# USB_mega8.net
KiCad netlist of a schematic drawn in Altium Designer
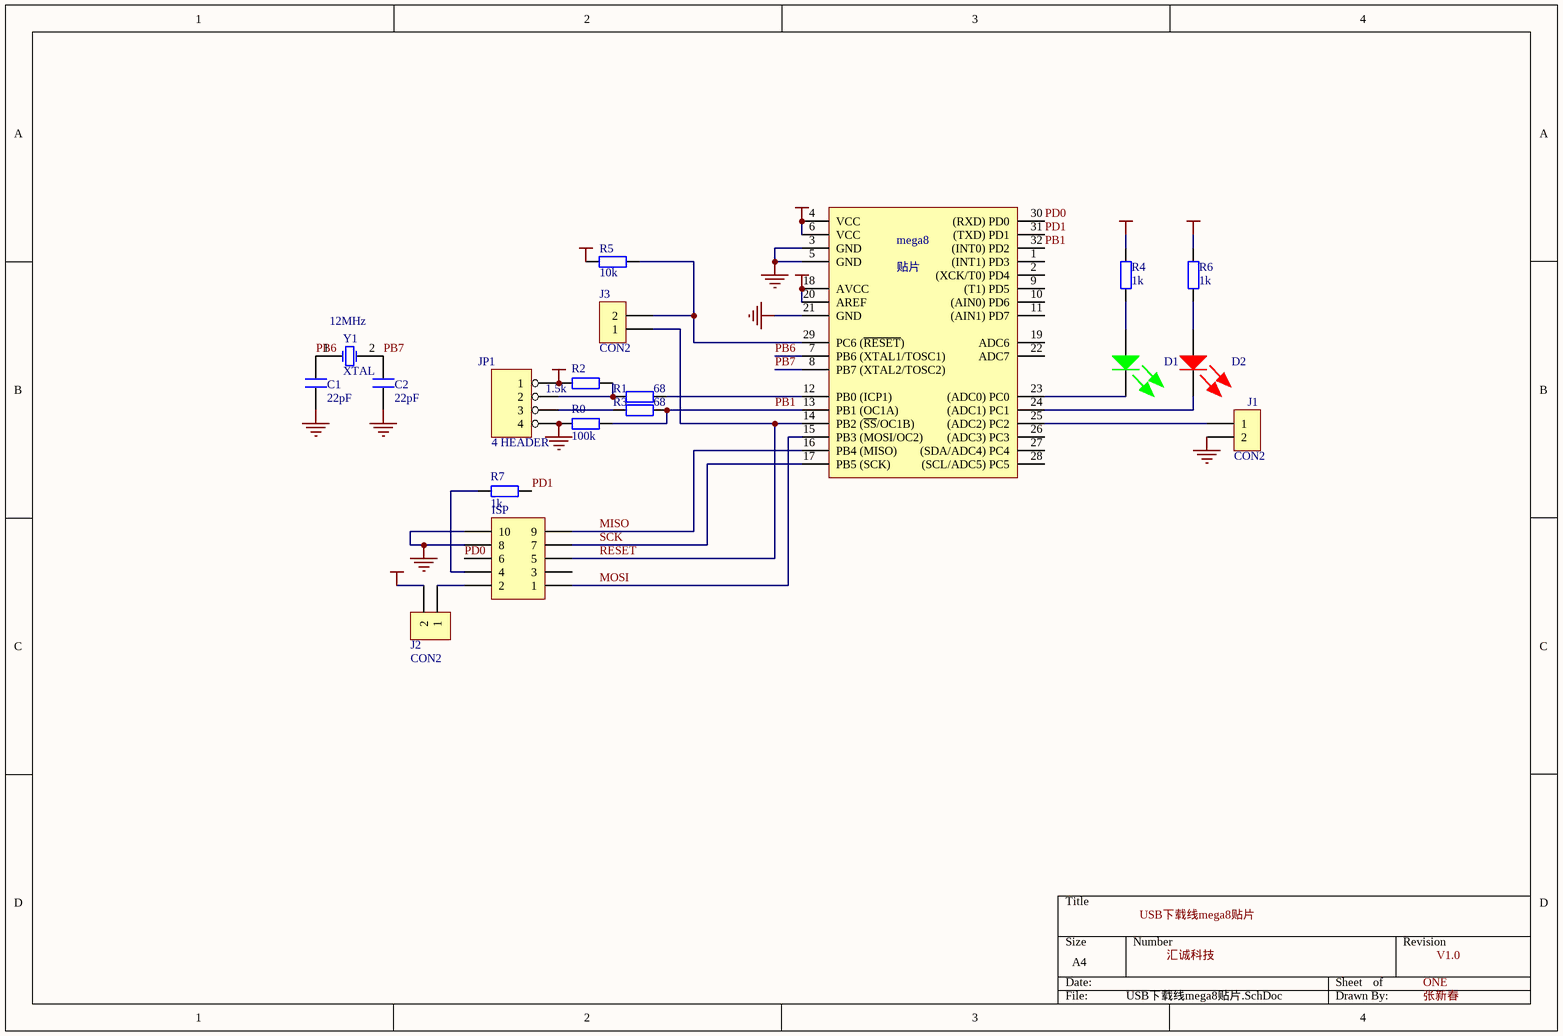
[diagram p0: USB下载线mega8贴片.SchDoc]

(export (version "E")
  (design (tool "Eeschema 10.0.6"))
  (components
    (comp (ref "C1")
      (value "22pF")
      (footprint "HDR1X2")
      (description "Capacitor SMD1206")
      (libsource (lib "*") (part "CAPSMD"))
    )
    (comp (ref "C2")
      (value "22pF")
      (footprint "HDR1X2")
      (description "Capacitor SMD1206")
      (libsource (lib "*") (part "CAPSMD"))
    )
    (comp (ref "D1")
      (value "~")
      (footprint "HDR1X2")
      (description "Zöld Led 3mm")
      (libsource (lib "*") (part "LED Zöld"))
    )
    (comp (ref "D2")
      (value "~")
      (footprint "HDR1X2")
      (description "Piros Led 3mm")
      (libsource (lib "*") (part "LED Piros"))
    )
    (comp (ref "ISP")
      (value "~")
      (footprint "HDR2X5")
      (description "Header, 5-Pin, Dual row, Right Angle")
      (fields (field (name "MANUFACTURER") "Generic Components"))
      (libsource (lib "*") (part "MLW10A"))
    )
    (comp (ref "J1")
      (value "CON2")
      (footprint "HDR1X2")
      (description "Connector")
      (libsource (lib "") (part "CON2_2"))
    )
    (comp (ref "J2")
      (value "CON2")
      (footprint "HDR1X2")
      (description "Connector")
      (libsource (lib "") (part "CON2_1"))
    )
    (comp (ref "J3")
      (value "CON2")
      (footprint "HDR1X2")
      (description "Connector")
      (libsource (lib "*") (part "CON2"))
    )
    (comp (ref "JP1")
      (value "4 HEADER")
      (footprint "USB")
      (description "4 Pin Header")
      (libsource (lib "*") (part "4 HEADER"))
    )
    (comp (ref "mega8")
      (value "贴片")
      (footprint "TQFP-32_0.8/7×7mm")
      (description "8 位微处理器/32引脚")
      (fields (field (name "发布者") "磊元工作室"))
      (libsource (lib "微控制处理器") (part "ATmega8-A"))
    )
    (comp (ref "R0")
      (value "100k")
      (footprint "HDR1X2")
      (description "Resistor SMD1206, 1% fémréteg")
      (libsource (lib "*") (part "RES"))
    )
    (comp (ref "R1")
      (value "68")
      (footprint "HDR1X2")
      (description "Resistor SMD1206, 1% fémréteg")
      (libsource (lib "*") (part "RES"))
    )
    (comp (ref "R2")
      (value "1.5k")
      (footprint "HDR1X2")
      (description "Resistor SMD1206, 1% fémréteg")
      (libsource (lib "*") (part "RES"))
    )
    (comp (ref "R3")
      (value "68")
      (footprint "HDR1X2")
      (description "Resistor SMD1206, 1% fémréteg")
      (libsource (lib "*") (part "RES"))
    )
    (comp (ref "R4")
      (value "1k")
      (footprint "HDR1X2")
      (description "Resistor SMD1206, 1% fémréteg")
      (libsource (lib "*") (part "RES"))
    )
    (comp (ref "R5")
      (value "10k")
      (footprint "HDR1X2")
      (description "Resistor SMD1206, 1% fémréteg")
      (libsource (lib "*") (part "RES"))
    )
    (comp (ref "R6")
      (value "1k")
      (footprint "HDR1X2")
      (description "Resistor SMD1206, 1% fémréteg")
      (libsource (lib "*") (part "RES"))
    )
    (comp (ref "R7")
      (value "1k")
      (footprint "HDR1X2")
      (description "Resistor SMD1206, 1% fémréteg")
      (libsource (lib "*") (part "RES"))
    )
    (comp (ref "Y1")
      (value "XTAL")
      (footprint "SPST-2")
      (description "Crystal Oscillator")
      (fields
        (field (name "MANUFACTURER") "Generic Components")
        (field (name "ALTIUM_VALUE") "12MHz")
        (field (name "PUBLISHER") "Altium Hobart Technology Centre")
      )
      (libsource (lib "*") (part "XTAL"))
    )
  )
  (nets
    (net (code "1") (name "/MISO") (class "Default")
      (node (ref "ISP") (pin "9") (pinfunction "9_9") (pintype "passive"))
      (node (ref "mega8") (pin "16") (pinfunction "PB4_(MISO)_16") (pintype "passive"))
    )
    (net (code "2") (name "/MOSI") (class "Default")
      (node (ref "ISP") (pin "1") (pinfunction "1_1") (pintype "passive"))
      (node (ref "mega8") (pin "15") (pinfunction "PB3_(MOSI/OC2)_15") (pintype "passive"))
    )
    (net (code "4") (name "/PB1") (class "Default")
      (node (ref "R0") (pin "2") (pinfunction "2_2") (pintype "passive"))
      (node (ref "R3") (pin "1") (pinfunction "1_1") (pintype "passive"))
      (node (ref "mega8") (pin "13") (pinfunction "PB1_(OC1A)_13") (pintype "passive"))
      (node (ref "mega8") (pin "32") (pinfunction "(INT0)_PD2_32") (pintype "passive"))
    )
    (net (code "5") (name "/PB6") (class "Default")
      (node (ref "C1") (pin "2") (pinfunction "2_2") (pintype "passive"))
      (node (ref "Y1") (pin "1") (pinfunction "OSC1_1") (pintype "passive"))
      (node (ref "mega8") (pin "7") (pinfunction "PB6_(XTAL1/TOSC1)_7") (pintype "passive"))
    )
    (net (code "6") (name "/PB7") (class "Default")
      (node (ref "C2") (pin "2") (pinfunction "2_2") (pintype "passive"))
      (node (ref "Y1") (pin "2") (pinfunction "OSC2_2") (pintype "passive"))
      (node (ref "mega8") (pin "8") (pinfunction "PB7_(XTAL2/TOSC2)_8") (pintype "passive"))
    )
    (net (code "7") (name "/PD0") (class "Default")
      (node (ref "ISP") (pin "6") (pinfunction "6_6") (pintype "passive"))
      (node (ref "mega8") (pin "30") (pinfunction "(RXD)_PD0_30") (pintype "passive"))
    )
    (net (code "8") (name "/PD1") (class "Default")
      (node (ref "R7") (pin "2") (pinfunction "2_2") (pintype "passive"))
      (node (ref "mega8") (pin "31") (pinfunction "(TXD)_PD1_31") (pintype "passive"))
    )
    (net (code "9") (name "/RESET") (class "Default")
      (node (ref "ISP") (pin "5") (pinfunction "5_5") (pintype "passive"))
      (node (ref "J3") (pin "1") (pinfunction "1_1") (pintype "passive"))
      (node (ref "mega8") (pin "14") (pinfunction "PB2_(~{SS}/OC1B)_14") (pintype "passive"))
    )
    (net (code "10") (name "/SCK") (class "Default")
      (node (ref "ISP") (pin "7") (pinfunction "7_7") (pintype "passive"))
      (node (ref "mega8") (pin "17") (pinfunction "PB5_(SCK)_17") (pintype "passive"))
    )
    (net (code "15") (name "GND") (class "Default")
      (node (ref "C1") (pin "1") (pinfunction "1_1") (pintype "passive"))
      (node (ref "C2") (pin "1") (pinfunction "1_1") (pintype "passive"))
      (node (ref "ISP") (pin "10") (pinfunction "10_10") (pintype "passive"))
      (node (ref "ISP") (pin "8") (pinfunction "8_8") (pintype "passive"))
      (node (ref "J1") (pin "2") (pinfunction "2_2") (pintype "passive"))
      (node (ref "JP1") (pin "4") (pinfunction "4_4") (pintype "passive"))
      (node (ref "R0") (pin "1") (pinfunction "1_1") (pintype "passive"))
      (node (ref "mega8") (pin "21") (pinfunction "GND_21") (pintype "passive"))
      (node (ref "mega8") (pin "3") (pinfunction "GND_3") (pintype "passive"))
      (node (ref "mega8") (pin "5") (pinfunction "GND_5") (pintype "passive"))
    )
    (net (code "16") (name "Net-(D1-Pad1)") (class "Default")
      (node (ref "D1") (pin "1") (pinfunction "1_1") (pintype "passive"))
      (node (ref "R4") (pin "1") (pinfunction "1_1") (pintype "passive"))
    )
    (net (code "17") (name "Net-(D2-Pad1)") (class "Default")
      (node (ref "D2") (pin "1") (pinfunction "1_1") (pintype "passive"))
      (node (ref "R6") (pin "1") (pinfunction "1_1") (pintype "passive"))
    )
    (net (code "18") (name "Net-(ISP-Pad2)") (class "Default")
      (node (ref "ISP") (pin "2") (pinfunction "2_2") (pintype "passive"))
      (node (ref "J2") (pin "1") (pinfunction "1_1") (pintype "passive"))
    )
    (net (code "19") (name "Net-(ISP-Pad4)") (class "Default")
      (node (ref "ISP") (pin "4") (pinfunction "4_4") (pintype "passive"))
      (node (ref "R7") (pin "1") (pinfunction "1_1") (pintype "passive"))
    )
    (net (code "20") (name "Net-(JP1-Pad2)") (class "Default")
      (node (ref "JP1") (pin "2") (pinfunction "2_2") (pintype "passive"))
      (node (ref "R1") (pin "1") (pinfunction "1_1") (pintype "passive"))
      (node (ref "R2") (pin "1") (pinfunction "1_1") (pintype "passive"))
    )
    (net (code "21") (name "Net-(JP1-Pad3)") (class "Default")
      (node (ref "JP1") (pin "3") (pinfunction "3_3") (pintype "passive"))
      (node (ref "R3") (pin "2") (pinfunction "2_2") (pintype "passive"))
    )
    (net (code "22") (name "Net-(mega8-(ADC0)_PC0)") (class "Default")
      (node (ref "D1") (pin "2") (pinfunction "2_2") (pintype "passive"))
      (node (ref "mega8") (pin "23") (pinfunction "(ADC0)_PC0_23") (pintype "passive"))
    )
    (net (code "23") (name "Net-(mega8-(ADC1)_PC1)") (class "Default")
      (node (ref "D2") (pin "2") (pinfunction "2_2") (pintype "passive"))
      (node (ref "mega8") (pin "24") (pinfunction "(ADC1)_PC1_24") (pintype "passive"))
    )
    (net (code "24") (name "Net-(mega8-(ADC2)_PC2)") (class "Default")
      (node (ref "J1") (pin "1") (pinfunction "1_1") (pintype "passive"))
      (node (ref "mega8") (pin "25") (pinfunction "(ADC2)_PC2_25") (pintype "passive"))
    )
    (net (code "25") (name "Net-(mega8-PB0_(ICP1))") (class "Default")
      (node (ref "R1") (pin "2") (pinfunction "2_2") (pintype "passive"))
      (node (ref "mega8") (pin "12") (pinfunction "PB0_(ICP1)_12") (pintype "passive"))
    )
    (net (code "26") (name "Net-(mega8-PC6_(~{RESET}))") (class "Default")
      (node (ref "J3") (pin "2") (pinfunction "2_2") (pintype "passive"))
      (node (ref "R5") (pin "1") (pinfunction "1_1") (pintype "passive"))
      (node (ref "mega8") (pin "29") (pinfunction "PC6_(~{RESET})_29") (pintype "passive"))
    )
    (net (code "27") (name "VCC") (class "Default")
      (node (ref "J2") (pin "2") (pinfunction "2_2") (pintype "passive"))
      (node (ref "JP1") (pin "1") (pinfunction "1_1") (pintype "passive"))
      (node (ref "R2") (pin "2") (pinfunction "2_2") (pintype "passive"))
      (node (ref "R4") (pin "2") (pinfunction "2_2") (pintype "passive"))
      (node (ref "R5") (pin "2") (pinfunction "2_2") (pintype "passive"))
      (node (ref "R6") (pin "2") (pinfunction "2_2") (pintype "passive"))
      (node (ref "mega8") (pin "18") (pinfunction "AVCC_18") (pintype "passive"))
      (node (ref "mega8") (pin "20") (pinfunction "AREF_20") (pintype "passive"))
      (node (ref "mega8") (pin "4") (pinfunction "VCC_4") (pintype "passive"))
      (node (ref "mega8") (pin "6") (pinfunction "VCC_6") (pintype "passive"))
    )
    (net (code "28") (name "unconnected-(ISP-Pad3)") (class "Default")
      (node (ref "ISP") (pin "3") (pinfunction "3_3") (pintype "passive"))
    )
    (net (code "29") (name "unconnected-(mega8-(ADC3)_PC3-Pad26)") (class "Default")
      (node (ref "mega8") (pin "26") (pinfunction "(ADC3)_PC3_26") (pintype "passive"))
    )
    (net (code "30") (name "unconnected-(mega8-(AIN0)_PD6-Pad10)") (class "Default")
      (node (ref "mega8") (pin "10") (pinfunction "(AIN0)_PD6_10") (pintype "passive"))
    )
    (net (code "31") (name "unconnected-(mega8-(AIN1)_PD7-Pad11)") (class "Default")
      (node (ref "mega8") (pin "11") (pinfunction "(AIN1)_PD7_11") (pintype "passive"))
    )
    (net (code "32") (name "unconnected-(mega8-(INT1)_PD3-Pad1)") (class "Default")
      (node (ref "mega8") (pin "1") (pinfunction "(INT1)_PD3_1") (pintype "passive"))
    )
    (net (code "33") (name "unconnected-(mega8-(SCL{slash}ADC5)_PC5-Pad28)") (class "Default")
      (node (ref "mega8") (pin "28") (pinfunction "(SCL/ADC5)_PC5_28") (pintype "passive"))
    )
    (net (code "34") (name "unconnected-(mega8-(SDA{slash}ADC4)_PC4-Pad27)") (class "Default")
      (node (ref "mega8") (pin "27") (pinfunction "(SDA/ADC4)_PC4_27") (pintype "passive"))
    )
    (net (code "35") (name "unconnected-(mega8-(T1)_PD5-Pad9)") (class "Default")
      (node (ref "mega8") (pin "9") (pinfunction "(T1)_PD5_9") (pintype "passive"))
    )
    (net (code "36") (name "unconnected-(mega8-(XCK{slash}T0)_PD4-Pad2)") (class "Default")
      (node (ref "mega8") (pin "2") (pinfunction "(XCK/T0)_PD4_2") (pintype "passive"))
    )
    (net (code "37") (name "unconnected-(mega8-ADC6-Pad19)") (class "Default")
      (node (ref "mega8") (pin "19") (pinfunction "ADC6_19") (pintype "passive"))
    )
    (net (code "38") (name "unconnected-(mega8-ADC7-Pad22)") (class "Default")
      (node (ref "mega8") (pin "22") (pinfunction "ADC7_22") (pintype "passive"))
    )
  )
)
